# Pololu_Magnetic_Encoder_AS5050.net
KiCad netlist of a schematic drawn in EAGLE
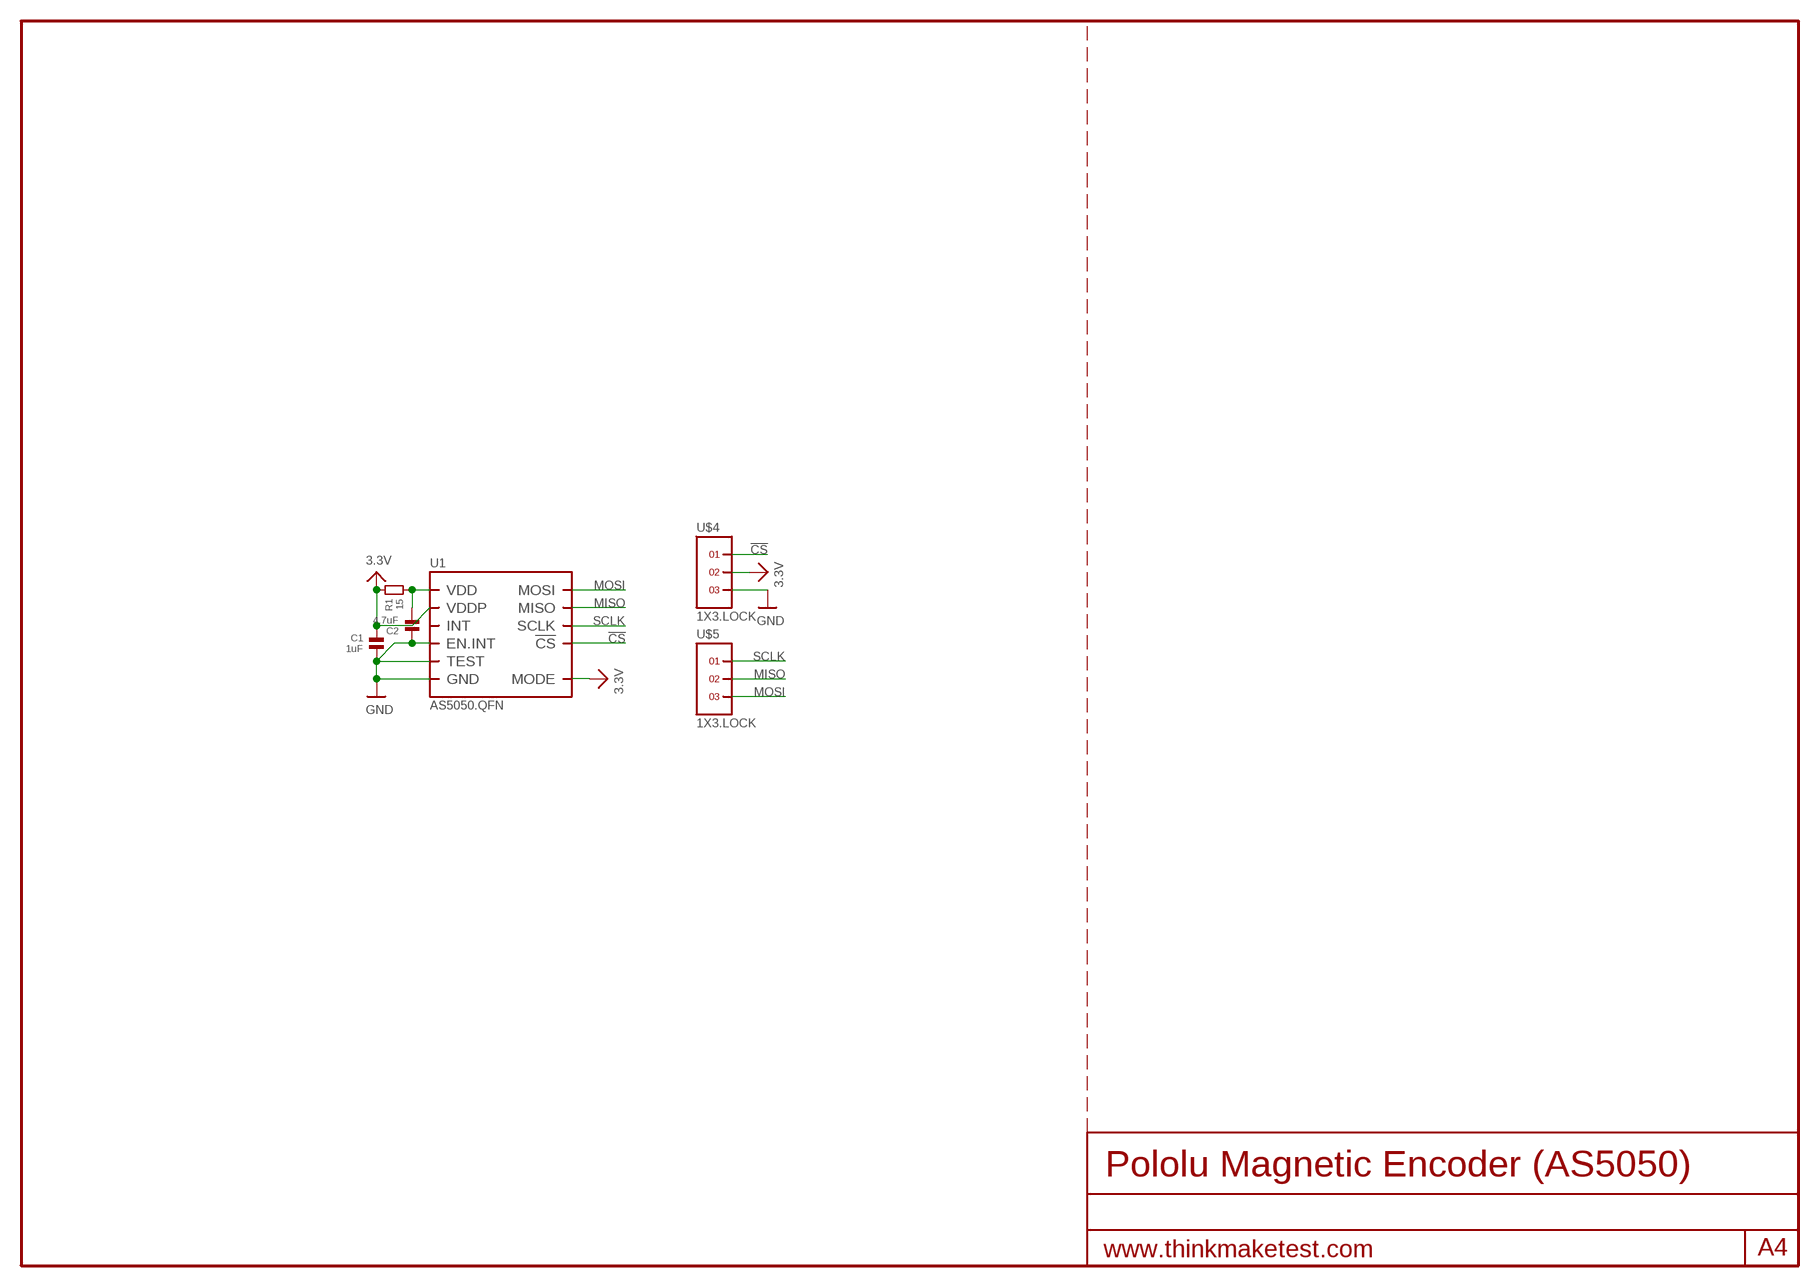
[diagram p0: schematic, sheet 1]

(export (version "E")
  (design (tool "Eeschema 10.0.6"))
  (components
    (comp (ref "C1")
      (value "1uF")
      (footprint "eagle-import:0603")
      (libsource (lib "eagle-import") (part "CAPACITOR.0603"))
    )
    (comp (ref "C2")
      (value "4.7uF")
      (footprint "eagle-import:0603")
      (libsource (lib "eagle-import") (part "CAPACITOR.0603"))
    )
    (comp (ref "R1")
      (value "15")
      (footprint "eagle-import:0603")
      (libsource (lib "eagle-import") (part "RESISTOR.0603"))
    )
    (comp (ref "U$4")
      (value "1X3.LOCK")
      (footprint "eagle-import:1X3.LOCK")
      (libsource (lib "eagle-import") (part "1X3.LOCK"))
    )
    (comp (ref "U$5")
      (value "1X3.LOCK")
      (footprint "eagle-import:1X3.LOCK")
      (libsource (lib "eagle-import") (part "1X3.LOCK"))
    )
    (comp (ref "U1")
      (value "AS5050.QFN")
      (footprint "eagle-import:QFN.16")
      (libsource (lib "eagle-import") (part "AS5050.QFN"))
    )
  )
  (nets
    (net (code "1") (name "/MISO") (class "Default")
      (node (ref "U$5") (pin "2") (pinfunction "2_2") (pintype "bidirectional"))
      (node (ref "U1") (pin "2") (pinfunction "MISO_2") (pintype "bidirectional"))
    )
    (net (code "2") (name "/MOSI") (class "Default")
      (node (ref "U$5") (pin "3") (pinfunction "3_3") (pintype "bidirectional"))
      (node (ref "U1") (pin "1") (pinfunction "MOSI_1") (pintype "bidirectional"))
    )
    (net (code "3") (name "/SCLK") (class "Default")
      (node (ref "U$5") (pin "1") (pinfunction "1_1") (pintype "bidirectional"))
      (node (ref "U1") (pin "3") (pinfunction "SCLK_3") (pintype "bidirectional"))
    )
    (net (code "4") (name "/~{CS}") (class "Default")
      (node (ref "U$4") (pin "1") (pinfunction "1_1") (pintype "bidirectional"))
      (node (ref "U1") (pin "4") (pinfunction "~{CS}_4") (pintype "bidirectional"))
    )
    (net (code "5") (name "3.3V") (class "Default")
      (node (ref "C1") (pin "1") (pinfunction "1_1") (pintype "bidirectional"))
      (node (ref "R1") (pin "1") (pinfunction "1_1") (pintype "bidirectional"))
      (node (ref "U$4") (pin "2") (pinfunction "2_2") (pintype "bidirectional"))
      (node (ref "U1") (pin "11") (pinfunction "VDDP_11") (pintype "bidirectional"))
      (node (ref "U1") (pin "14") (pinfunction "MODE_14") (pintype "bidirectional"))
    )
    (net (code "6") (name "GND") (class "Default")
      (node (ref "C1") (pin "2") (pinfunction "2_2") (pintype "bidirectional"))
      (node (ref "C2") (pin "1") (pinfunction "1_1") (pintype "bidirectional"))
      (node (ref "U$4") (pin "3") (pinfunction "3_3") (pintype "bidirectional"))
      (node (ref "U1") (pin "10") (pinfunction "EN.INT_10") (pintype "bidirectional"))
      (node (ref "U1") (pin "13") (pinfunction "GND_13") (pintype "bidirectional"))
      (node (ref "U1") (pin "9") (pinfunction "TEST_9") (pintype "bidirectional"))
    )
    (net (code "7") (name "Net-(U1-VDD)") (class "Default")
      (node (ref "C2") (pin "2") (pinfunction "2_2") (pintype "bidirectional"))
      (node (ref "R1") (pin "2") (pinfunction "2_2") (pintype "bidirectional"))
      (node (ref "U1") (pin "12") (pinfunction "VDD_12") (pintype "bidirectional"))
    )
    (net (code "8") (name "unconnected-(U1-INT-Pad15)") (class "Default")
      (node (ref "U1") (pin "15") (pinfunction "INT_15") (pintype "bidirectional"))
    )
  )
)
